# stick.net
KiCad netlist of a schematic drawn in EAGLE
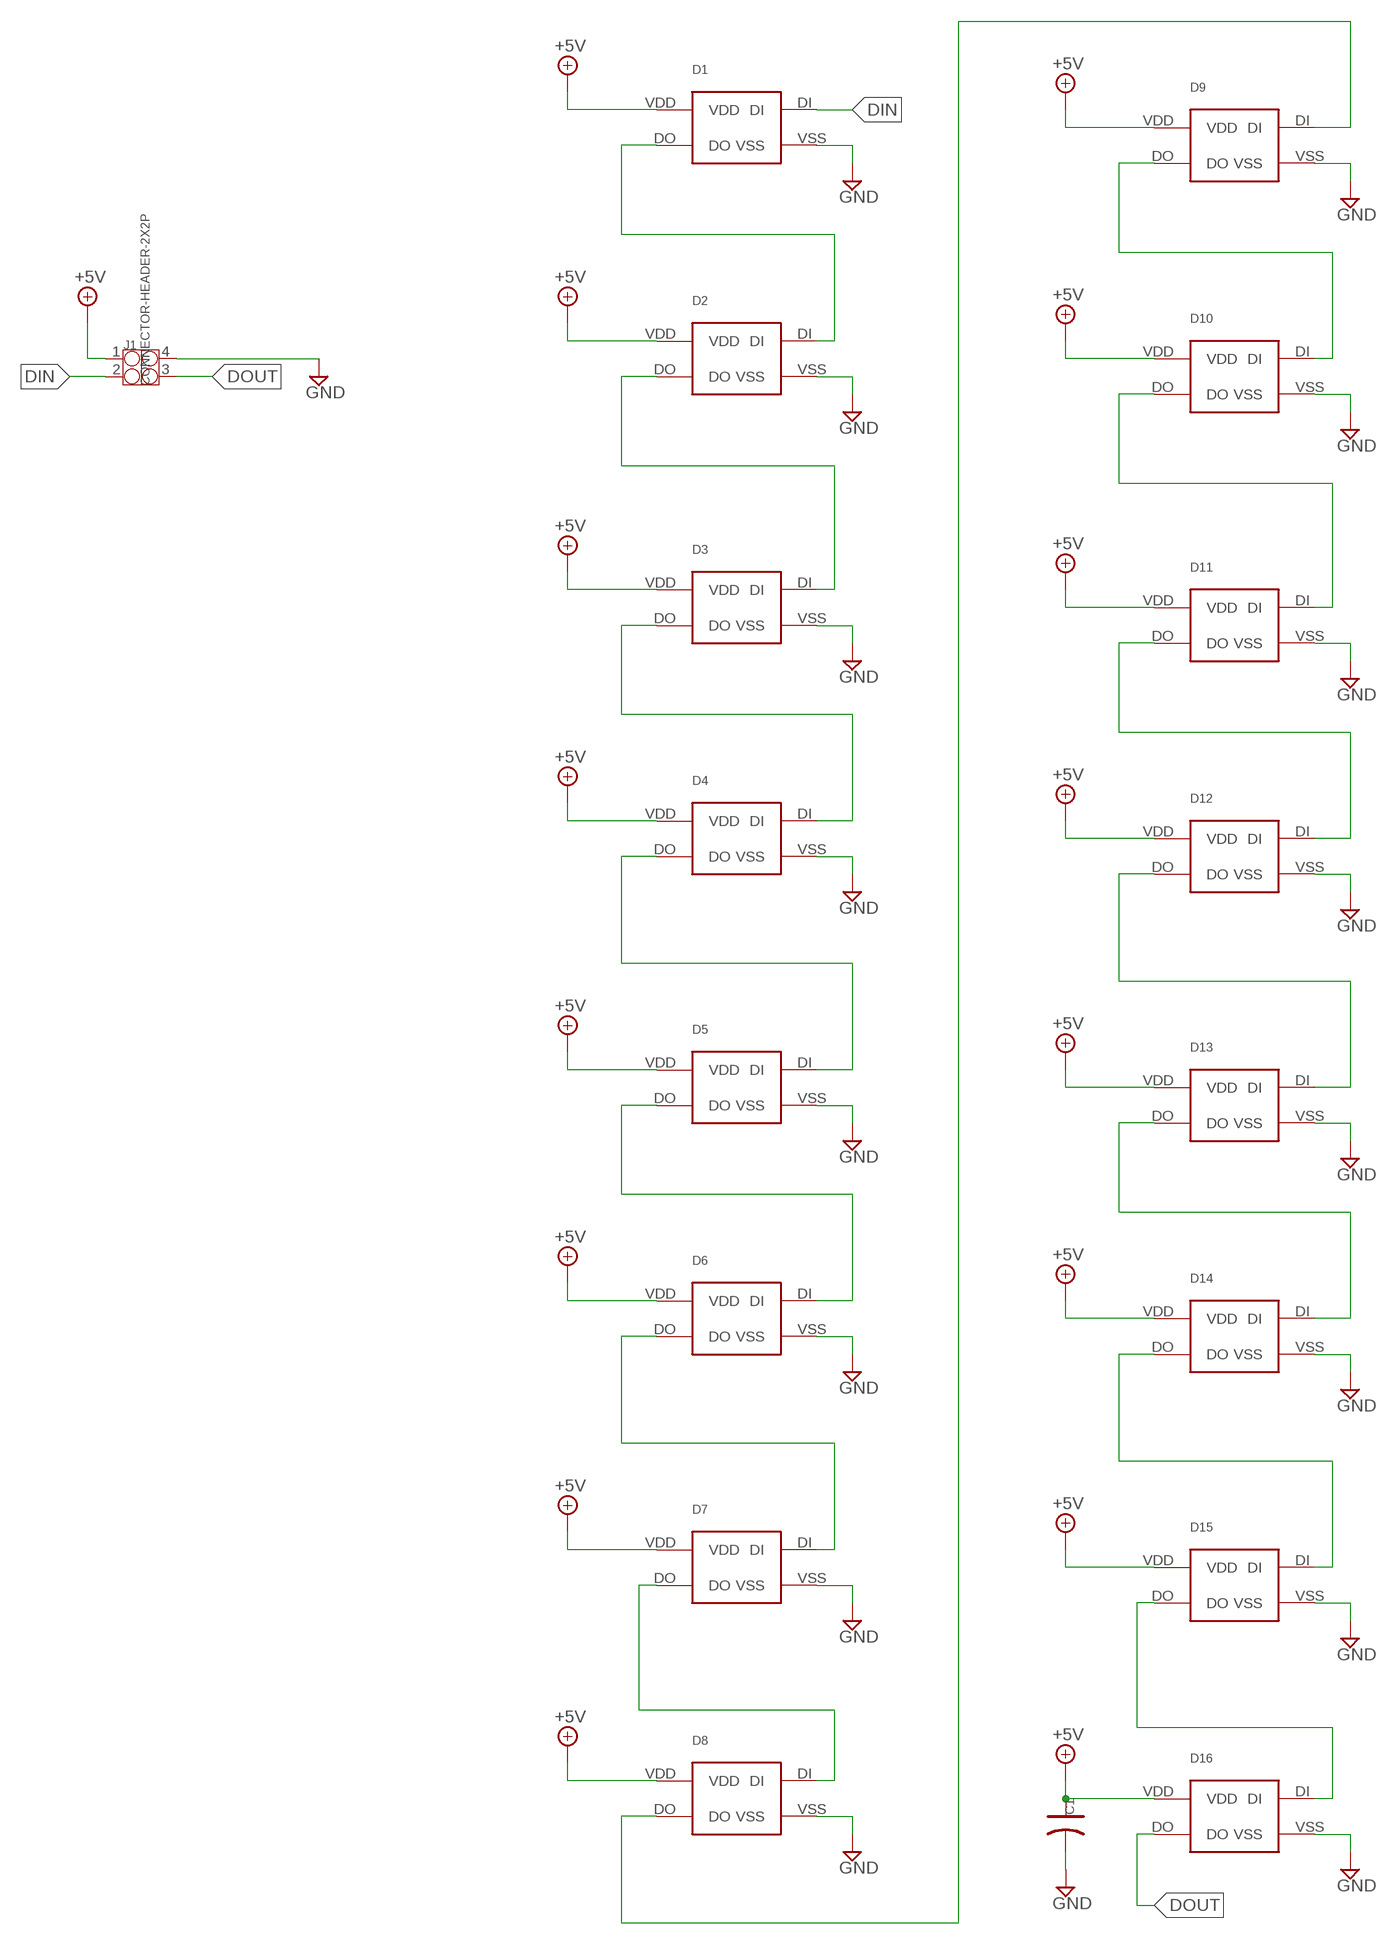
[diagram p0: schematic, sheet 1]

(export (version "E")
  (design (tool "Eeschema 10.0.6"))
  (components
    (comp (ref "C1")
      (value "C-POLAR-A")
      (footprint "eagle-import:AVX-A")
      (libsource (lib "eagle-import") (part "C-POLAR-A"))
    )
    (comp (ref "D1")
      (value "WS2812B")
      (footprint "eagle-import:WS2812B")
      (libsource (lib "eagle-import") (part "WS2812B"))
    )
    (comp (ref "D2")
      (value "WS2812B")
      (footprint "eagle-import:WS2812B")
      (libsource (lib "eagle-import") (part "WS2812B"))
    )
    (comp (ref "D3")
      (value "WS2812B")
      (footprint "eagle-import:WS2812B")
      (libsource (lib "eagle-import") (part "WS2812B"))
    )
    (comp (ref "D4")
      (value "WS2812B")
      (footprint "eagle-import:WS2812B")
      (libsource (lib "eagle-import") (part "WS2812B"))
    )
    (comp (ref "D5")
      (value "WS2812B")
      (footprint "eagle-import:WS2812B")
      (libsource (lib "eagle-import") (part "WS2812B"))
    )
    (comp (ref "D6")
      (value "WS2812B")
      (footprint "eagle-import:WS2812B")
      (libsource (lib "eagle-import") (part "WS2812B"))
    )
    (comp (ref "D7")
      (value "WS2812B")
      (footprint "eagle-import:WS2812B")
      (libsource (lib "eagle-import") (part "WS2812B"))
    )
    (comp (ref "D8")
      (value "WS2812B")
      (footprint "eagle-import:WS2812B")
      (libsource (lib "eagle-import") (part "WS2812B"))
    )
    (comp (ref "D9")
      (value "WS2812B")
      (footprint "eagle-import:WS2812B")
      (libsource (lib "eagle-import") (part "WS2812B"))
    )
    (comp (ref "D10")
      (value "WS2812B")
      (footprint "eagle-import:WS2812B")
      (libsource (lib "eagle-import") (part "WS2812B"))
    )
    (comp (ref "D11")
      (value "WS2812B")
      (footprint "eagle-import:WS2812B")
      (libsource (lib "eagle-import") (part "WS2812B"))
    )
    (comp (ref "D12")
      (value "WS2812B")
      (footprint "eagle-import:WS2812B")
      (libsource (lib "eagle-import") (part "WS2812B"))
    )
    (comp (ref "D13")
      (value "WS2812B")
      (footprint "eagle-import:WS2812B")
      (libsource (lib "eagle-import") (part "WS2812B"))
    )
    (comp (ref "D14")
      (value "WS2812B")
      (footprint "eagle-import:WS2812B")
      (libsource (lib "eagle-import") (part "WS2812B"))
    )
    (comp (ref "D15")
      (value "WS2812B")
      (footprint "eagle-import:WS2812B")
      (libsource (lib "eagle-import") (part "WS2812B"))
    )
    (comp (ref "D16")
      (value "WS2812B")
      (footprint "eagle-import:WS2812B")
      (libsource (lib "eagle-import") (part "WS2812B"))
    )
    (comp (ref "J1")
      (value "CONNECTOR-HEADER-2X2P")
      (footprint "eagle-import:2X2P-2.54")
      (libsource (lib "eagle-import") (part "CONNECTOR-HEADER-2X2P"))
    )
  )
  (nets
    (net (code "1") (name "+5V") (class "Default")
      (node (ref "C1") (pin "+") (pinfunction "1_+") (pintype "bidirectional"))
      (node (ref "D1") (pin "VDD") (pinfunction "VDD_VDD") (pintype "bidirectional"))
      (node (ref "D10") (pin "VDD") (pinfunction "VDD_VDD") (pintype "bidirectional"))
      (node (ref "D11") (pin "VDD") (pinfunction "VDD_VDD") (pintype "bidirectional"))
      (node (ref "D12") (pin "VDD") (pinfunction "VDD_VDD") (pintype "bidirectional"))
      (node (ref "D13") (pin "VDD") (pinfunction "VDD_VDD") (pintype "bidirectional"))
      (node (ref "D14") (pin "VDD") (pinfunction "VDD_VDD") (pintype "bidirectional"))
      (node (ref "D15") (pin "VDD") (pinfunction "VDD_VDD") (pintype "bidirectional"))
      (node (ref "D16") (pin "VDD") (pinfunction "VDD_VDD") (pintype "bidirectional"))
      (node (ref "D2") (pin "VDD") (pinfunction "VDD_VDD") (pintype "bidirectional"))
      (node (ref "D3") (pin "VDD") (pinfunction "VDD_VDD") (pintype "bidirectional"))
      (node (ref "D4") (pin "VDD") (pinfunction "VDD_VDD") (pintype "bidirectional"))
      (node (ref "D5") (pin "VDD") (pinfunction "VDD_VDD") (pintype "bidirectional"))
      (node (ref "D6") (pin "VDD") (pinfunction "VDD_VDD") (pintype "bidirectional"))
      (node (ref "D7") (pin "VDD") (pinfunction "VDD_VDD") (pintype "bidirectional"))
      (node (ref "D8") (pin "VDD") (pinfunction "VDD_VDD") (pintype "bidirectional"))
      (node (ref "D9") (pin "VDD") (pinfunction "VDD_VDD") (pintype "bidirectional"))
      (node (ref "J1") (pin "1") (pinfunction "1_1") (pintype "bidirectional"))
    )
    (net (code "2") (name "DIN") (class "Default")
      (node (ref "D1") (pin "DI") (pinfunction "DI_DI") (pintype "bidirectional"))
      (node (ref "J1") (pin "2") (pinfunction "2_2") (pintype "bidirectional"))
    )
    (net (code "3") (name "DOUT") (class "Default")
      (node (ref "D16") (pin "DO") (pinfunction "DO_DO") (pintype "bidirectional"))
      (node (ref "J1") (pin "3") (pinfunction "3_3") (pintype "bidirectional"))
    )
    (net (code "4") (name "GND") (class "Default")
      (node (ref "C1") (pin "-") (pinfunction "2_-") (pintype "bidirectional"))
      (node (ref "D1") (pin "VSS") (pinfunction "VSS_VSS") (pintype "bidirectional"))
      (node (ref "D10") (pin "VSS") (pinfunction "VSS_VSS") (pintype "bidirectional"))
      (node (ref "D11") (pin "VSS") (pinfunction "VSS_VSS") (pintype "bidirectional"))
      (node (ref "D12") (pin "VSS") (pinfunction "VSS_VSS") (pintype "bidirectional"))
      (node (ref "D13") (pin "VSS") (pinfunction "VSS_VSS") (pintype "bidirectional"))
      (node (ref "D14") (pin "VSS") (pinfunction "VSS_VSS") (pintype "bidirectional"))
      (node (ref "D15") (pin "VSS") (pinfunction "VSS_VSS") (pintype "bidirectional"))
      (node (ref "D16") (pin "VSS") (pinfunction "VSS_VSS") (pintype "bidirectional"))
      (node (ref "D2") (pin "VSS") (pinfunction "VSS_VSS") (pintype "bidirectional"))
      (node (ref "D3") (pin "VSS") (pinfunction "VSS_VSS") (pintype "bidirectional"))
      (node (ref "D4") (pin "VSS") (pinfunction "VSS_VSS") (pintype "bidirectional"))
      (node (ref "D5") (pin "VSS") (pinfunction "VSS_VSS") (pintype "bidirectional"))
      (node (ref "D6") (pin "VSS") (pinfunction "VSS_VSS") (pintype "bidirectional"))
      (node (ref "D7") (pin "VSS") (pinfunction "VSS_VSS") (pintype "bidirectional"))
      (node (ref "D8") (pin "VSS") (pinfunction "VSS_VSS") (pintype "bidirectional"))
      (node (ref "D9") (pin "VSS") (pinfunction "VSS_VSS") (pintype "bidirectional"))
      (node (ref "J1") (pin "4") (pinfunction "4_4") (pintype "bidirectional"))
    )
    (net (code "5") (name "Net-(D1-PadDO)") (class "Default")
      (node (ref "D1") (pin "DO") (pinfunction "DO_DO") (pintype "bidirectional"))
      (node (ref "D2") (pin "DI") (pinfunction "DI_DI") (pintype "bidirectional"))
    )
    (net (code "6") (name "Net-(D2-PadDO)") (class "Default")
      (node (ref "D2") (pin "DO") (pinfunction "DO_DO") (pintype "bidirectional"))
      (node (ref "D3") (pin "DI") (pinfunction "DI_DI") (pintype "bidirectional"))
    )
    (net (code "7") (name "Net-(D3-PadDO)") (class "Default")
      (node (ref "D3") (pin "DO") (pinfunction "DO_DO") (pintype "bidirectional"))
      (node (ref "D4") (pin "DI") (pinfunction "DI_DI") (pintype "bidirectional"))
    )
    (net (code "8") (name "Net-(D4-PadDO)") (class "Default")
      (node (ref "D4") (pin "DO") (pinfunction "DO_DO") (pintype "bidirectional"))
      (node (ref "D5") (pin "DI") (pinfunction "DI_DI") (pintype "bidirectional"))
    )
    (net (code "9") (name "Net-(D5-PadDO)") (class "Default")
      (node (ref "D5") (pin "DO") (pinfunction "DO_DO") (pintype "bidirectional"))
      (node (ref "D6") (pin "DI") (pinfunction "DI_DI") (pintype "bidirectional"))
    )
    (net (code "10") (name "Net-(D6-PadDO)") (class "Default")
      (node (ref "D6") (pin "DO") (pinfunction "DO_DO") (pintype "bidirectional"))
      (node (ref "D7") (pin "DI") (pinfunction "DI_DI") (pintype "bidirectional"))
    )
    (net (code "11") (name "Net-(D7-PadDO)") (class "Default")
      (node (ref "D7") (pin "DO") (pinfunction "DO_DO") (pintype "bidirectional"))
      (node (ref "D8") (pin "DI") (pinfunction "DI_DI") (pintype "bidirectional"))
    )
    (net (code "12") (name "Net-(D8-PadDO)") (class "Default")
      (node (ref "D8") (pin "DO") (pinfunction "DO_DO") (pintype "bidirectional"))
      (node (ref "D9") (pin "DI") (pinfunction "DI_DI") (pintype "bidirectional"))
    )
    (net (code "13") (name "Net-(D10-PadDI)") (class "Default")
      (node (ref "D10") (pin "DI") (pinfunction "DI_DI") (pintype "bidirectional"))
      (node (ref "D9") (pin "DO") (pinfunction "DO_DO") (pintype "bidirectional"))
    )
    (net (code "14") (name "Net-(D10-PadDO)") (class "Default")
      (node (ref "D10") (pin "DO") (pinfunction "DO_DO") (pintype "bidirectional"))
      (node (ref "D11") (pin "DI") (pinfunction "DI_DI") (pintype "bidirectional"))
    )
    (net (code "15") (name "Net-(D11-PadDO)") (class "Default")
      (node (ref "D11") (pin "DO") (pinfunction "DO_DO") (pintype "bidirectional"))
      (node (ref "D12") (pin "DI") (pinfunction "DI_DI") (pintype "bidirectional"))
    )
    (net (code "16") (name "Net-(D12-PadDO)") (class "Default")
      (node (ref "D12") (pin "DO") (pinfunction "DO_DO") (pintype "bidirectional"))
      (node (ref "D13") (pin "DI") (pinfunction "DI_DI") (pintype "bidirectional"))
    )
    (net (code "17") (name "Net-(D13-PadDO)") (class "Default")
      (node (ref "D13") (pin "DO") (pinfunction "DO_DO") (pintype "bidirectional"))
      (node (ref "D14") (pin "DI") (pinfunction "DI_DI") (pintype "bidirectional"))
    )
    (net (code "18") (name "Net-(D14-PadDO)") (class "Default")
      (node (ref "D14") (pin "DO") (pinfunction "DO_DO") (pintype "bidirectional"))
      (node (ref "D15") (pin "DI") (pinfunction "DI_DI") (pintype "bidirectional"))
    )
    (net (code "19") (name "Net-(D15-PadDO)") (class "Default")
      (node (ref "D15") (pin "DO") (pinfunction "DO_DO") (pintype "bidirectional"))
      (node (ref "D16") (pin "DI") (pinfunction "DI_DI") (pintype "bidirectional"))
    )
  )
)
